# balancing_robot_pcb.net
KiCad netlist of a schematic drawn in EAGLE
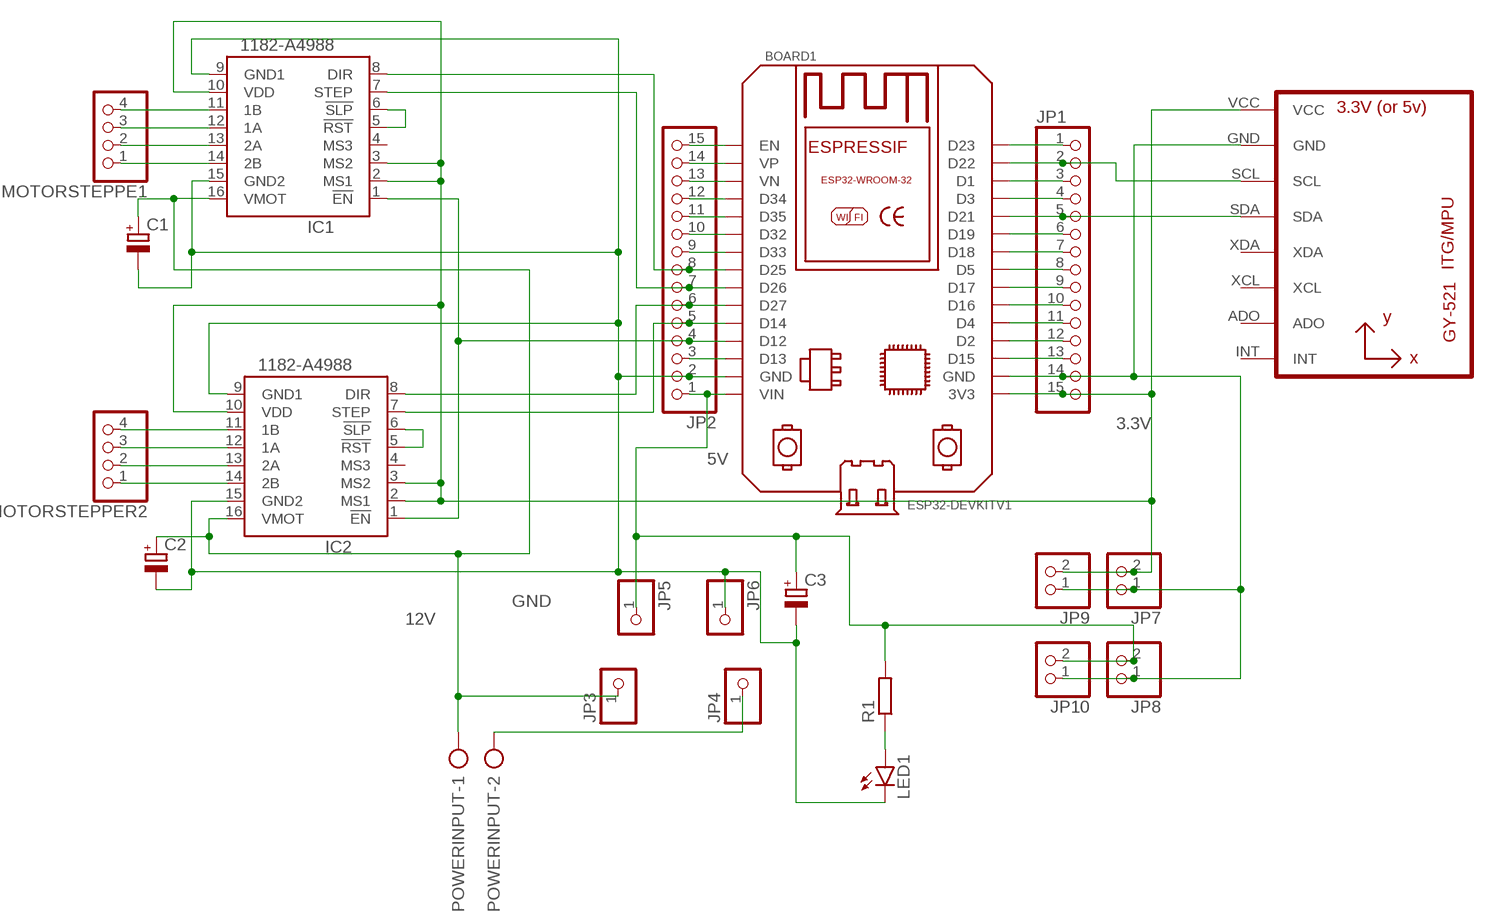
[diagram p0: schematic, sheet 1]

(export (version "E")
  (design (tool "Eeschema 10.0.6"))
  (components
    (comp (ref "BOARD1")
      (value "ESP32DEVKITV1")
      (footprint "eagle-import:ESP32-DEVKITV1")
      (libsource (lib "eagle-import") (part "ESP32DEVKITV1"))
    )
    (comp (ref "C1")
      (value "CPOL-EUE3.5-8")
      (footprint "eagle-import:E3,5-8")
      (libsource (lib "eagle-import") (part "CPOL-EUE3.5-8"))
    )
    (comp (ref "C2")
      (value "CPOL-EUE3.5-8")
      (footprint "eagle-import:E3,5-8")
      (libsource (lib "eagle-import") (part "CPOL-EUE3.5-8"))
    )
    (comp (ref "C3")
      (value "CPOL-EUE3.5-8")
      (footprint "eagle-import:E3,5-8")
      (libsource (lib "eagle-import") (part "CPOL-EUE3.5-8"))
    )
    (comp (ref "IC1")
      (value "1182-A4988")
      (footprint "eagle-import:A4988")
      (libsource (lib "eagle-import") (part "1182-A4988"))
    )
    (comp (ref "IC2")
      (value "1182-A4988")
      (footprint "eagle-import:A4988")
      (libsource (lib "eagle-import") (part "1182-A4988"))
    )
    (comp (ref "JP1")
      (value "PINHD-1X15")
      (footprint "eagle-import:1X15")
      (libsource (lib "eagle-import") (part "PINHD-1X15"))
    )
    (comp (ref "JP2")
      (value "PINHD-1X15")
      (footprint "eagle-import:1X15")
      (libsource (lib "eagle-import") (part "PINHD-1X15"))
    )
    (comp (ref "JP3")
      (value "PINHD-1X1")
      (footprint "eagle-import:1X01")
      (libsource (lib "eagle-import") (part "PINHD-1X1"))
    )
    (comp (ref "JP4")
      (value "PINHD-1X1")
      (footprint "eagle-import:1X01")
      (libsource (lib "eagle-import") (part "PINHD-1X1"))
    )
    (comp (ref "JP5")
      (value "PINHD-1X1")
      (footprint "eagle-import:1X01")
      (libsource (lib "eagle-import") (part "PINHD-1X1"))
    )
    (comp (ref "JP6")
      (value "PINHD-1X1")
      (footprint "eagle-import:1X01")
      (libsource (lib "eagle-import") (part "PINHD-1X1"))
    )
    (comp (ref "JP7")
      (value "PINHD-1X2")
      (footprint "eagle-import:1X02")
      (libsource (lib "eagle-import") (part "PINHD-1X2"))
    )
    (comp (ref "JP8")
      (value "PINHD-1X2")
      (footprint "eagle-import:1X02")
      (libsource (lib "eagle-import") (part "PINHD-1X2"))
    )
    (comp (ref "JP9")
      (value "PINHD-1X2")
      (footprint "eagle-import:1X02")
      (libsource (lib "eagle-import") (part "PINHD-1X2"))
    )
    (comp (ref "JP10")
      (value "PINHD-1X2")
      (footprint "eagle-import:1X02")
      (libsource (lib "eagle-import") (part "PINHD-1X2"))
    )
    (comp (ref "LED1")
      (value "LED5MM")
      (footprint "eagle-import:LED5MM")
      (libsource (lib "eagle-import") (part "LED5MM"))
    )
    (comp (ref "MOTORSTEPPE1")
      (value "PINHD-1X4")
      (footprint "eagle-import:1X04")
      (libsource (lib "eagle-import") (part "PINHD-1X4"))
    )
    (comp (ref "MOTORSTEPPER2")
      (value "PINHD-1X4")
      (footprint "eagle-import:1X04")
      (libsource (lib "eagle-import") (part "PINHD-1X4"))
    )
    (comp (ref "POWERINPUT")
      (value "AK500/2-H")
      (footprint "eagle-import:AK500_2-H")
      (libsource (lib "eagle-import") (part "AK500/2-H"))
    )
    (comp (ref "R1")
      (value "R-EU_0204/7")
      (footprint "eagle-import:0204_7")
      (libsource (lib "eagle-import") (part "R-EU_0204/7"))
    )
    (comp (ref "U1")
      (value "GY-521MPU6050")
      (footprint "eagle-import:GY-521")
      (libsource (lib "eagle-import") (part "GY-521MPU6050"))
    )
  )
  (nets
    (net (code "1") (name "/3.3V") (class "Default")
      (node (ref "BOARD1") (pin "3V3") (pinfunction "3V3_3V3") (pintype "bidirectional"))
      (node (ref "IC1") (pin "10") (pinfunction "VDD_10") (pintype "power_in"))
      (node (ref "IC1") (pin "2") (pinfunction "MS1_2") (pintype "passive"))
      (node (ref "IC1") (pin "3") (pinfunction "MS2_3") (pintype "passive"))
      (node (ref "IC2") (pin "10") (pinfunction "VDD_10") (pintype "power_in"))
      (node (ref "IC2") (pin "2") (pinfunction "MS1_2") (pintype "passive"))
      (node (ref "IC2") (pin "3") (pinfunction "MS2_3") (pintype "passive"))
      (node (ref "JP1") (pin "15") (pinfunction "15_15") (pintype "passive"))
      (node (ref "JP7") (pin "2") (pinfunction "2_2") (pintype "passive"))
      (node (ref "JP9") (pin "2") (pinfunction "2_2") (pintype "passive"))
      (node (ref "U1") (pin "VCC") (pinfunction "VCC_VCC") (pintype "bidirectional"))
    )
    (net (code "2") (name "/5V") (class "Default")
      (node (ref "BOARD1") (pin "VIN") (pinfunction "VIN_VIN") (pintype "bidirectional"))
      (node (ref "C3") (pin "+") (pinfunction "+_+") (pintype "passive"))
      (node (ref "JP10") (pin "2") (pinfunction "2_2") (pintype "passive"))
      (node (ref "JP2") (pin "1") (pinfunction "1_1") (pintype "passive"))
      (node (ref "JP5") (pin "1") (pinfunction "1_1") (pintype "passive"))
      (node (ref "JP8") (pin "2") (pinfunction "2_2") (pintype "passive"))
      (node (ref "R1") (pin "2") (pinfunction "2_2") (pintype "passive"))
    )
    (net (code "3") (name "/12V") (class "Default")
      (node (ref "C1") (pin "+") (pinfunction "+_+") (pintype "passive"))
      (node (ref "C2") (pin "+") (pinfunction "+_+") (pintype "passive"))
      (node (ref "IC1") (pin "16") (pinfunction "VMOT_16") (pintype "power_in"))
      (node (ref "IC2") (pin "16") (pinfunction "VMOT_16") (pintype "power_in"))
      (node (ref "JP3") (pin "1") (pinfunction "1_1") (pintype "passive"))
      (node (ref "POWERINPUT") (pin "1") (pinfunction "KL_1") (pintype "passive"))
    )
    (net (code "4") (name "/GND") (class "Default")
      (node (ref "BOARD1") (pin "GND") (pinfunction "GND_GND") (pintype "bidirectional"))
      (node (ref "C1") (pin "-") (pinfunction "-_-") (pintype "passive"))
      (node (ref "C2") (pin "-") (pinfunction "-_-") (pintype "passive"))
      (node (ref "C3") (pin "-") (pinfunction "-_-") (pintype "passive"))
      (node (ref "IC1") (pin "15") (pinfunction "GND2_15") (pintype "power_in"))
      (node (ref "IC1") (pin "9") (pinfunction "GND1_9") (pintype "power_in"))
      (node (ref "IC2") (pin "15") (pinfunction "GND2_15") (pintype "power_in"))
      (node (ref "IC2") (pin "9") (pinfunction "GND1_9") (pintype "power_in"))
      (node (ref "JP2") (pin "2") (pinfunction "2_2") (pintype "passive"))
      (node (ref "JP6") (pin "1") (pinfunction "1_1") (pintype "passive"))
      (node (ref "LED1") (pin "K") (pinfunction "C_K") (pintype "passive"))
    )
    (net (code "5") (name "Net-(BOARD1-GND-PadGND@1)") (class "Default")
      (node (ref "BOARD1") (pin "GND@1") (pinfunction "GND_GND@1") (pintype "bidirectional"))
      (node (ref "JP1") (pin "14") (pinfunction "14_14") (pintype "passive"))
      (node (ref "JP10") (pin "1") (pinfunction "1_1") (pintype "passive"))
      (node (ref "JP7") (pin "1") (pinfunction "1_1") (pintype "passive"))
      (node (ref "JP8") (pin "1") (pinfunction "1_1") (pintype "passive"))
      (node (ref "JP9") (pin "1") (pinfunction "1_1") (pintype "passive"))
      (node (ref "U1") (pin "GND") (pinfunction "GND_GND") (pintype "bidirectional"))
    )
    (net (code "6") (name "Net-(BOARD1-PadD1)") (class "Default")
      (node (ref "BOARD1") (pin "D1") (pinfunction "D1_D1") (pintype "bidirectional"))
      (node (ref "JP1") (pin "3") (pinfunction "3_3") (pintype "passive"))
    )
    (net (code "7") (name "Net-(BOARD1-PadD2)") (class "Default")
      (node (ref "BOARD1") (pin "D2") (pinfunction "D2_D2") (pintype "bidirectional"))
      (node (ref "JP1") (pin "12") (pinfunction "12_12") (pintype "passive"))
    )
    (net (code "8") (name "Net-(BOARD1-PadD3)") (class "Default")
      (node (ref "BOARD1") (pin "D3") (pinfunction "D3_D3") (pintype "bidirectional"))
      (node (ref "JP1") (pin "4") (pinfunction "4_4") (pintype "passive"))
    )
    (net (code "9") (name "Net-(BOARD1-PadD4)") (class "Default")
      (node (ref "BOARD1") (pin "D4") (pinfunction "D4_D4") (pintype "bidirectional"))
      (node (ref "JP1") (pin "11") (pinfunction "11_11") (pintype "passive"))
    )
    (net (code "10") (name "Net-(BOARD1-PadD5)") (class "Default")
      (node (ref "BOARD1") (pin "D5") (pinfunction "D5_D5") (pintype "bidirectional"))
      (node (ref "JP1") (pin "8") (pinfunction "8_8") (pintype "passive"))
    )
    (net (code "11") (name "Net-(BOARD1-PadD13)") (class "Default")
      (node (ref "BOARD1") (pin "D13") (pinfunction "D13_D13") (pintype "bidirectional"))
      (node (ref "JP2") (pin "3") (pinfunction "3_3") (pintype "passive"))
    )
    (net (code "12") (name "Net-(BOARD1-PadD15)") (class "Default")
      (node (ref "BOARD1") (pin "D15") (pinfunction "D15_D15") (pintype "bidirectional"))
      (node (ref "JP1") (pin "13") (pinfunction "13_13") (pintype "passive"))
    )
    (net (code "13") (name "Net-(BOARD1-PadD16)") (class "Default")
      (node (ref "BOARD1") (pin "D16") (pinfunction "D16_D16") (pintype "bidirectional"))
      (node (ref "JP1") (pin "10") (pinfunction "10_10") (pintype "passive"))
    )
    (net (code "14") (name "Net-(BOARD1-PadD17)") (class "Default")
      (node (ref "BOARD1") (pin "D17") (pinfunction "D17_D17") (pintype "bidirectional"))
      (node (ref "JP1") (pin "9") (pinfunction "9_9") (pintype "passive"))
    )
    (net (code "15") (name "Net-(BOARD1-PadD18)") (class "Default")
      (node (ref "BOARD1") (pin "D18") (pinfunction "D18_D18") (pintype "bidirectional"))
      (node (ref "JP1") (pin "7") (pinfunction "7_7") (pintype "passive"))
    )
    (net (code "16") (name "Net-(BOARD1-PadD19)") (class "Default")
      (node (ref "BOARD1") (pin "D19") (pinfunction "D19_D19") (pintype "bidirectional"))
      (node (ref "JP1") (pin "6") (pinfunction "6_6") (pintype "passive"))
    )
    (net (code "17") (name "Net-(BOARD1-PadD21)") (class "Default")
      (node (ref "BOARD1") (pin "D21") (pinfunction "D21_D21") (pintype "bidirectional"))
      (node (ref "JP1") (pin "5") (pinfunction "5_5") (pintype "passive"))
      (node (ref "U1") (pin "SDA") (pinfunction "SDA_SDA") (pintype "bidirectional"))
    )
    (net (code "18") (name "Net-(BOARD1-PadD22)") (class "Default")
      (node (ref "BOARD1") (pin "D22") (pinfunction "D22_D22") (pintype "bidirectional"))
      (node (ref "JP1") (pin "2") (pinfunction "2_2") (pintype "passive"))
      (node (ref "U1") (pin "SCL") (pinfunction "SCL_SCL") (pintype "bidirectional"))
    )
    (net (code "19") (name "Net-(BOARD1-PadD23)") (class "Default")
      (node (ref "BOARD1") (pin "D23") (pinfunction "D23_D23") (pintype "bidirectional"))
      (node (ref "JP1") (pin "1") (pinfunction "1_1") (pintype "passive"))
    )
    (net (code "20") (name "Net-(BOARD1-PadD32)") (class "Default")
      (node (ref "BOARD1") (pin "D32") (pinfunction "D32_D32") (pintype "bidirectional"))
      (node (ref "JP2") (pin "10") (pinfunction "10_10") (pintype "passive"))
    )
    (net (code "21") (name "Net-(BOARD1-PadD33)") (class "Default")
      (node (ref "BOARD1") (pin "D33") (pinfunction "D33_D33") (pintype "bidirectional"))
      (node (ref "JP2") (pin "9") (pinfunction "9_9") (pintype "passive"))
    )
    (net (code "22") (name "Net-(BOARD1-PadD34)") (class "Default")
      (node (ref "BOARD1") (pin "D34") (pinfunction "D34_D34") (pintype "bidirectional"))
      (node (ref "JP2") (pin "12") (pinfunction "12_12") (pintype "passive"))
    )
    (net (code "23") (name "Net-(BOARD1-PadD35)") (class "Default")
      (node (ref "BOARD1") (pin "D35") (pinfunction "D35_D35") (pintype "bidirectional"))
      (node (ref "JP2") (pin "11") (pinfunction "11_11") (pintype "passive"))
    )
    (net (code "24") (name "Net-(BOARD1-PadEN)") (class "Default")
      (node (ref "BOARD1") (pin "EN") (pinfunction "EN_EN") (pintype "bidirectional"))
      (node (ref "JP2") (pin "15") (pinfunction "15_15") (pintype "passive"))
    )
    (net (code "25") (name "Net-(BOARD1-PadVN)") (class "Default")
      (node (ref "BOARD1") (pin "VN") (pinfunction "VN_VN") (pintype "bidirectional"))
      (node (ref "JP2") (pin "13") (pinfunction "13_13") (pintype "passive"))
    )
    (net (code "26") (name "Net-(BOARD1-PadVP)") (class "Default")
      (node (ref "BOARD1") (pin "VP") (pinfunction "VP_VP") (pintype "bidirectional"))
      (node (ref "JP2") (pin "14") (pinfunction "14_14") (pintype "passive"))
    )
    (net (code "27") (name "Net-(IC1-1A)") (class "Default")
      (node (ref "IC1") (pin "12") (pinfunction "1A_12") (pintype "output"))
      (node (ref "MOTORSTEPPE1") (pin "3") (pinfunction "3_3") (pintype "passive"))
    )
    (net (code "28") (name "Net-(IC1-1B)") (class "Default")
      (node (ref "IC1") (pin "11") (pinfunction "1B_11") (pintype "output"))
      (node (ref "MOTORSTEPPE1") (pin "4") (pinfunction "4_4") (pintype "passive"))
    )
    (net (code "29") (name "Net-(IC1-2A)") (class "Default")
      (node (ref "IC1") (pin "13") (pinfunction "2A_13") (pintype "output"))
      (node (ref "MOTORSTEPPE1") (pin "2") (pinfunction "2_2") (pintype "passive"))
    )
    (net (code "30") (name "Net-(IC1-2B)") (class "Default")
      (node (ref "IC1") (pin "14") (pinfunction "2B_14") (pintype "output"))
      (node (ref "MOTORSTEPPE1") (pin "1") (pinfunction "1_1") (pintype "passive"))
    )
    (net (code "31") (name "Net-(IC1-DIR)") (class "Default")
      (node (ref "BOARD1") (pin "D25") (pinfunction "D25_D25") (pintype "bidirectional"))
      (node (ref "IC1") (pin "8") (pinfunction "DIR_8") (pintype "input"))
      (node (ref "JP2") (pin "8") (pinfunction "8_8") (pintype "passive"))
    )
    (net (code "32") (name "Net-(IC1-STEP)") (class "Default")
      (node (ref "BOARD1") (pin "D26") (pinfunction "D26_D26") (pintype "bidirectional"))
      (node (ref "IC1") (pin "7") (pinfunction "STEP_7") (pintype "input"))
      (node (ref "JP2") (pin "7") (pinfunction "7_7") (pintype "passive"))
    )
    (net (code "33") (name "Net-(IC1-~{EN})") (class "Default")
      (node (ref "BOARD1") (pin "D12") (pinfunction "D12_D12") (pintype "bidirectional"))
      (node (ref "IC1") (pin "1") (pinfunction "~{EN}_1") (pintype "passive"))
      (node (ref "IC2") (pin "1") (pinfunction "~{EN}_1") (pintype "passive"))
      (node (ref "JP2") (pin "4") (pinfunction "4_4") (pintype "passive"))
    )
    (net (code "34") (name "Net-(IC1-~{RST})") (class "Default")
      (node (ref "IC1") (pin "5") (pinfunction "~{RST}_5") (pintype "passive"))
      (node (ref "IC1") (pin "6") (pinfunction "~{SLP}_6") (pintype "passive"))
    )
    (net (code "35") (name "Net-(IC2-1A)") (class "Default")
      (node (ref "IC2") (pin "12") (pinfunction "1A_12") (pintype "output"))
      (node (ref "MOTORSTEPPER2") (pin "3") (pinfunction "3_3") (pintype "passive"))
    )
    (net (code "36") (name "Net-(IC2-1B)") (class "Default")
      (node (ref "IC2") (pin "11") (pinfunction "1B_11") (pintype "output"))
      (node (ref "MOTORSTEPPER2") (pin "4") (pinfunction "4_4") (pintype "passive"))
    )
    (net (code "37") (name "Net-(IC2-2A)") (class "Default")
      (node (ref "IC2") (pin "13") (pinfunction "2A_13") (pintype "output"))
      (node (ref "MOTORSTEPPER2") (pin "2") (pinfunction "2_2") (pintype "passive"))
    )
    (net (code "38") (name "Net-(IC2-2B)") (class "Default")
      (node (ref "IC2") (pin "14") (pinfunction "2B_14") (pintype "output"))
      (node (ref "MOTORSTEPPER2") (pin "1") (pinfunction "1_1") (pintype "passive"))
    )
    (net (code "39") (name "Net-(IC2-DIR)") (class "Default")
      (node (ref "BOARD1") (pin "D27") (pinfunction "D27_D27") (pintype "bidirectional"))
      (node (ref "IC2") (pin "8") (pinfunction "DIR_8") (pintype "input"))
      (node (ref "JP2") (pin "6") (pinfunction "6_6") (pintype "passive"))
    )
    (net (code "40") (name "Net-(IC2-STEP)") (class "Default")
      (node (ref "BOARD1") (pin "D14") (pinfunction "D14_D14") (pintype "bidirectional"))
      (node (ref "IC2") (pin "7") (pinfunction "STEP_7") (pintype "input"))
      (node (ref "JP2") (pin "5") (pinfunction "5_5") (pintype "passive"))
    )
    (net (code "41") (name "Net-(IC2-~{RST})") (class "Default")
      (node (ref "IC2") (pin "5") (pinfunction "~{RST}_5") (pintype "passive"))
      (node (ref "IC2") (pin "6") (pinfunction "~{SLP}_6") (pintype "passive"))
    )
    (net (code "42") (name "Net-(LED1-PadA)") (class "Default")
      (node (ref "LED1") (pin "A") (pinfunction "A_A") (pintype "passive"))
      (node (ref "R1") (pin "1") (pinfunction "1_1") (pintype "passive"))
    )
    (net (code "43") (name "Net-(POWERINPUTB-KL)") (class "Default")
      (node (ref "JP4") (pin "1") (pinfunction "1_1") (pintype "passive"))
      (node (ref "POWERINPUT") (pin "2") (pinfunction "KL_2") (pintype "passive"))
    )
    (net (code "44") (name "unconnected-(IC1-MS3-Pad4)") (class "Default")
      (node (ref "IC1") (pin "4") (pinfunction "MS3_4") (pintype "passive"))
    )
    (net (code "45") (name "unconnected-(IC2-MS3-Pad4)") (class "Default")
      (node (ref "IC2") (pin "4") (pinfunction "MS3_4") (pintype "passive"))
    )
    (net (code "46") (name "unconnected-(U1-PadADO)") (class "Default")
      (node (ref "U1") (pin "ADO") (pinfunction "ADO_ADO") (pintype "bidirectional"))
    )
    (net (code "47") (name "unconnected-(U1-PadINT)") (class "Default")
      (node (ref "U1") (pin "INT") (pinfunction "INT_INT") (pintype "bidirectional"))
    )
    (net (code "48") (name "unconnected-(U1-PadXCL)") (class "Default")
      (node (ref "U1") (pin "XCL") (pinfunction "XCL_XCL") (pintype "bidirectional"))
    )
    (net (code "49") (name "unconnected-(U1-PadXDA)") (class "Default")
      (node (ref "U1") (pin "XDA") (pinfunction "XDA_XDA") (pintype "bidirectional"))
    )
  )
)
